# dcdc.net
KiCad netlist of a schematic drawn in Altium Designer
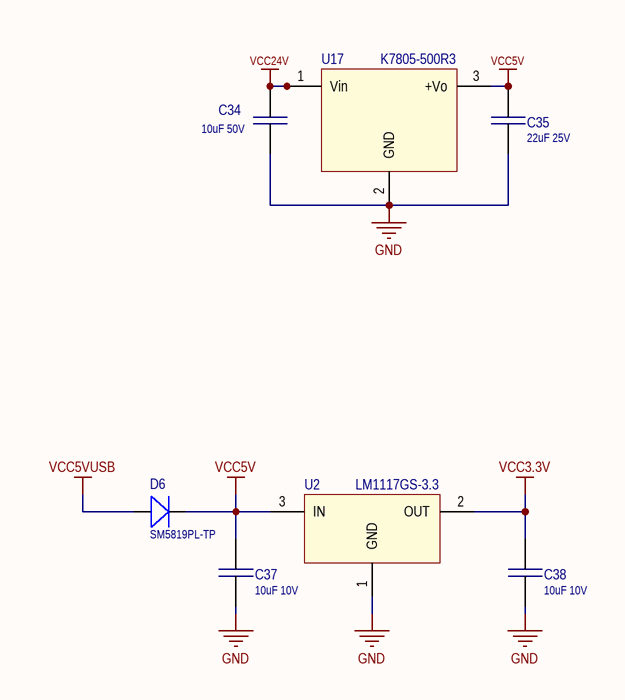
[diagram p0: dcdc.schdoc]

(export (version "E")
  (design (tool "Eeschema 10.0.6"))
  (components
    (comp (ref "C34")
      (value "10uF 50V")
      (footprint "C_1206")
      (description "Capacitor")
      (fields (field (name "PART") "CC1206KKX5R9BB106") (field (name "ALTERNATIVE PART") "CL31A106KBHNNNE"))
      (libsource (lib "capacitors") (part "C1206"))
    )
    (comp (ref "C35")
      (value "22uF 25V")
      (footprint "C_1206")
      (description "Capacitor")
      (fields (field (name "PART") "CC1206KKX5R8BB226") (field (name "ALTERNATIVE PART") "CL31A226KAHNNNE"))
      (libsource (lib "capacitors") (part "C1206"))
    )
    (comp (ref "C37")
      (value "10uF 10V")
      (footprint "C_0805")
      (description "Capacitor")
      (fields (field (name "PART") "CC0805KKX5R6BB106"))
      (libsource (lib "capacitors") (part "C0805"))
    )
    (comp (ref "C38")
      (value "10uF 10V")
      (footprint "C_0805")
      (description "Capacitor")
      (fields (field (name "PART") "CC0805KKX5R6BB106"))
      (libsource (lib "capacitors") (part "C0805"))
    )
    (comp (ref "D6")
      (value "SM5819PL-TP")
      (footprint "SOD-123")
      (description "Diode")
      (libsource (lib "AX_Altium_v2.3") (part "D_SOD123"))
    )
    (comp (ref "U2")
      (value "LM1117GS-3.3")
      (footprint "SOT 223")
      (description "LDO")
      (libsource (lib "dcdc_ldo_ref") (part "LDO 3.3v"))
    )
    (comp (ref "U17")
      (value "K7805-500R3")
      (footprint "K7805500R3")
      (description "Non-isolated dc-dc")
      (libsource (lib "dcdc_ldo_ref") (part "K78xx-500R3"))
    )
  )
  (nets
    (net (code "1") (name "GND") (class "Default")
      (node (ref "C34") (pin "2") (pinfunction "2_2") (pintype "passive"))
      (node (ref "C35") (pin "1") (pinfunction "1_1") (pintype "passive"))
      (node (ref "C37") (pin "1") (pinfunction "1_1") (pintype "passive"))
      (node (ref "C38") (pin "1") (pinfunction "1_1") (pintype "passive"))
      (node (ref "U17") (pin "2") (pinfunction "GND_2") (pintype "passive"))
      (node (ref "U2") (pin "1") (pinfunction "GND_1") (pintype "passive"))
    )
    (net (code "2") (name "VCC3.3V") (class "Default")
      (node (ref "C38") (pin "2") (pinfunction "2_2") (pintype "passive"))
      (node (ref "U2") (pin "2") (pinfunction "OUT_2") (pintype "passive"))
    )
    (net (code "3") (name "VCC5V") (class "Default")
      (node (ref "C35") (pin "2") (pinfunction "2_2") (pintype "passive"))
      (node (ref "C37") (pin "2") (pinfunction "2_2") (pintype "passive"))
      (node (ref "D6") (pin "2") (pinfunction "K_2") (pintype "passive"))
      (node (ref "U17") (pin "3") (pinfunction "+Vo_3") (pintype "passive"))
      (node (ref "U2") (pin "3") (pinfunction "IN_3") (pintype "passive"))
    )
    (net (code "4") (name "VCC5VUSB") (class "Default")
      (node (ref "D6") (pin "1") (pinfunction "A_1") (pintype "passive"))
    )
    (net (code "5") (name "VCC24V") (class "Default")
      (node (ref "C34") (pin "1") (pinfunction "1_1") (pintype "passive"))
      (node (ref "U17") (pin "1") (pinfunction "Vin_1") (pintype "passive"))
    )
  )
)
